# IR.net
KiCad netlist of a schematic drawn in EAGLE
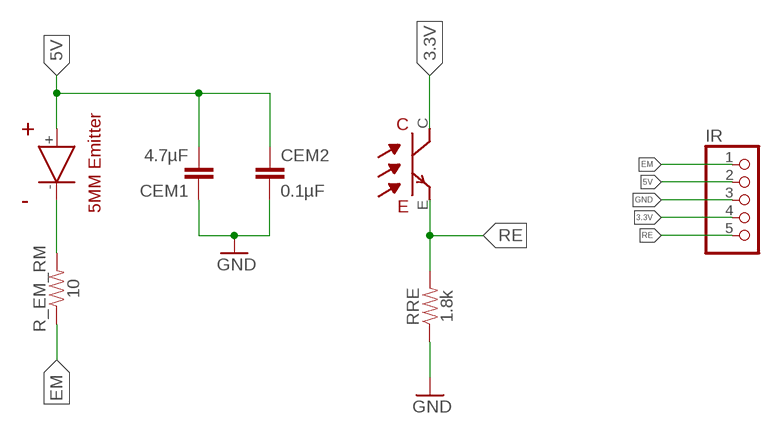
[diagram p0: schematic, sheet 1]

(export (version "E")
  (design (tool "Eeschema 10.0.6"))
  (components
    (comp (ref "CEM1")
      (value "4.7µF")
      (footprint "eagle-import:0805")
      (libsource (lib "eagle-import") (part "0.33UF/330NF-0805-50V-10%"))
    )
    (comp (ref "CEM2")
      (value "0.1µF")
      (footprint "eagle-import:0805")
      (libsource (lib "eagle-import") (part "0.33UF/330NF-0805-50V-10%"))
    )
    (comp (ref "IR")
      (value "PINHD-1X5")
      (footprint "eagle-import:1X05")
      (libsource (lib "eagle-import") (part "PINHD-1X5"))
    )
    (comp (ref "RRE")
      (value "1.8k")
      (footprint "eagle-import:0805")
      (libsource (lib "eagle-import") (part "0.75OHM-0805-1/4W-1%"))
    )
    (comp (ref "R_EM_RM")
      (value "10")
      (footprint "eagle-import:0805")
      (libsource (lib "eagle-import") (part "0.75OHM-0805-1/4W-1%"))
    )
    (comp (ref "U$21")
      (value "EMITTER")
      (footprint "eagle-import:EMITTER")
      (libsource (lib "eagle-import") (part "EMITTER"))
    )
    (comp (ref "U$23")
      (value "RECEIVER")
      (footprint "eagle-import:RECEIVER")
      (libsource (lib "eagle-import") (part "RECEIVER"))
    )
  )
  (nets
    (net (code "1") (name "3.3V") (class "Default")
      (node (ref "IR") (pin "4") (pinfunction "4_4") (pintype "passive"))
      (node (ref "U$23") (pin "C") (pinfunction "C_C") (pintype "bidirectional"))
    )
    (net (code "2") (name "5V") (class "Default")
      (node (ref "CEM1") (pin "2") (pinfunction "2_2") (pintype "passive"))
      (node (ref "CEM2") (pin "1") (pinfunction "1_1") (pintype "passive"))
      (node (ref "IR") (pin "2") (pinfunction "2_2") (pintype "passive"))
      (node (ref "U$21") (pin "+") (pinfunction "+_+") (pintype "bidirectional"))
    )
    (net (code "3") (name "EM") (class "Default")
      (node (ref "IR") (pin "1") (pinfunction "1_1") (pintype "passive"))
      (node (ref "R_EM_RM") (pin "1") (pinfunction "1_1") (pintype "passive"))
    )
    (net (code "4") (name "GND") (class "Default")
      (node (ref "CEM1") (pin "1") (pinfunction "1_1") (pintype "passive"))
      (node (ref "CEM2") (pin "2") (pinfunction "2_2") (pintype "passive"))
      (node (ref "IR") (pin "3") (pinfunction "3_3") (pintype "passive"))
      (node (ref "RRE") (pin "1") (pinfunction "1_1") (pintype "passive"))
    )
    (net (code "5") (name "Net-(R_EM_RM-Pad2)") (class "Default")
      (node (ref "R_EM_RM") (pin "2") (pinfunction "2_2") (pintype "passive"))
      (node (ref "U$21") (pin "-") (pinfunction "-_-") (pintype "bidirectional"))
    )
    (net (code "6") (name "RE") (class "Default")
      (node (ref "IR") (pin "5") (pinfunction "5_5") (pintype "passive"))
      (node (ref "RRE") (pin "2") (pinfunction "2_2") (pintype "passive"))
      (node (ref "U$23") (pin "E") (pinfunction "E_E") (pintype "bidirectional"))
    )
  )
)
